# xmega_ethernet.net
KiCad netlist of a schematic drawn in EAGLE
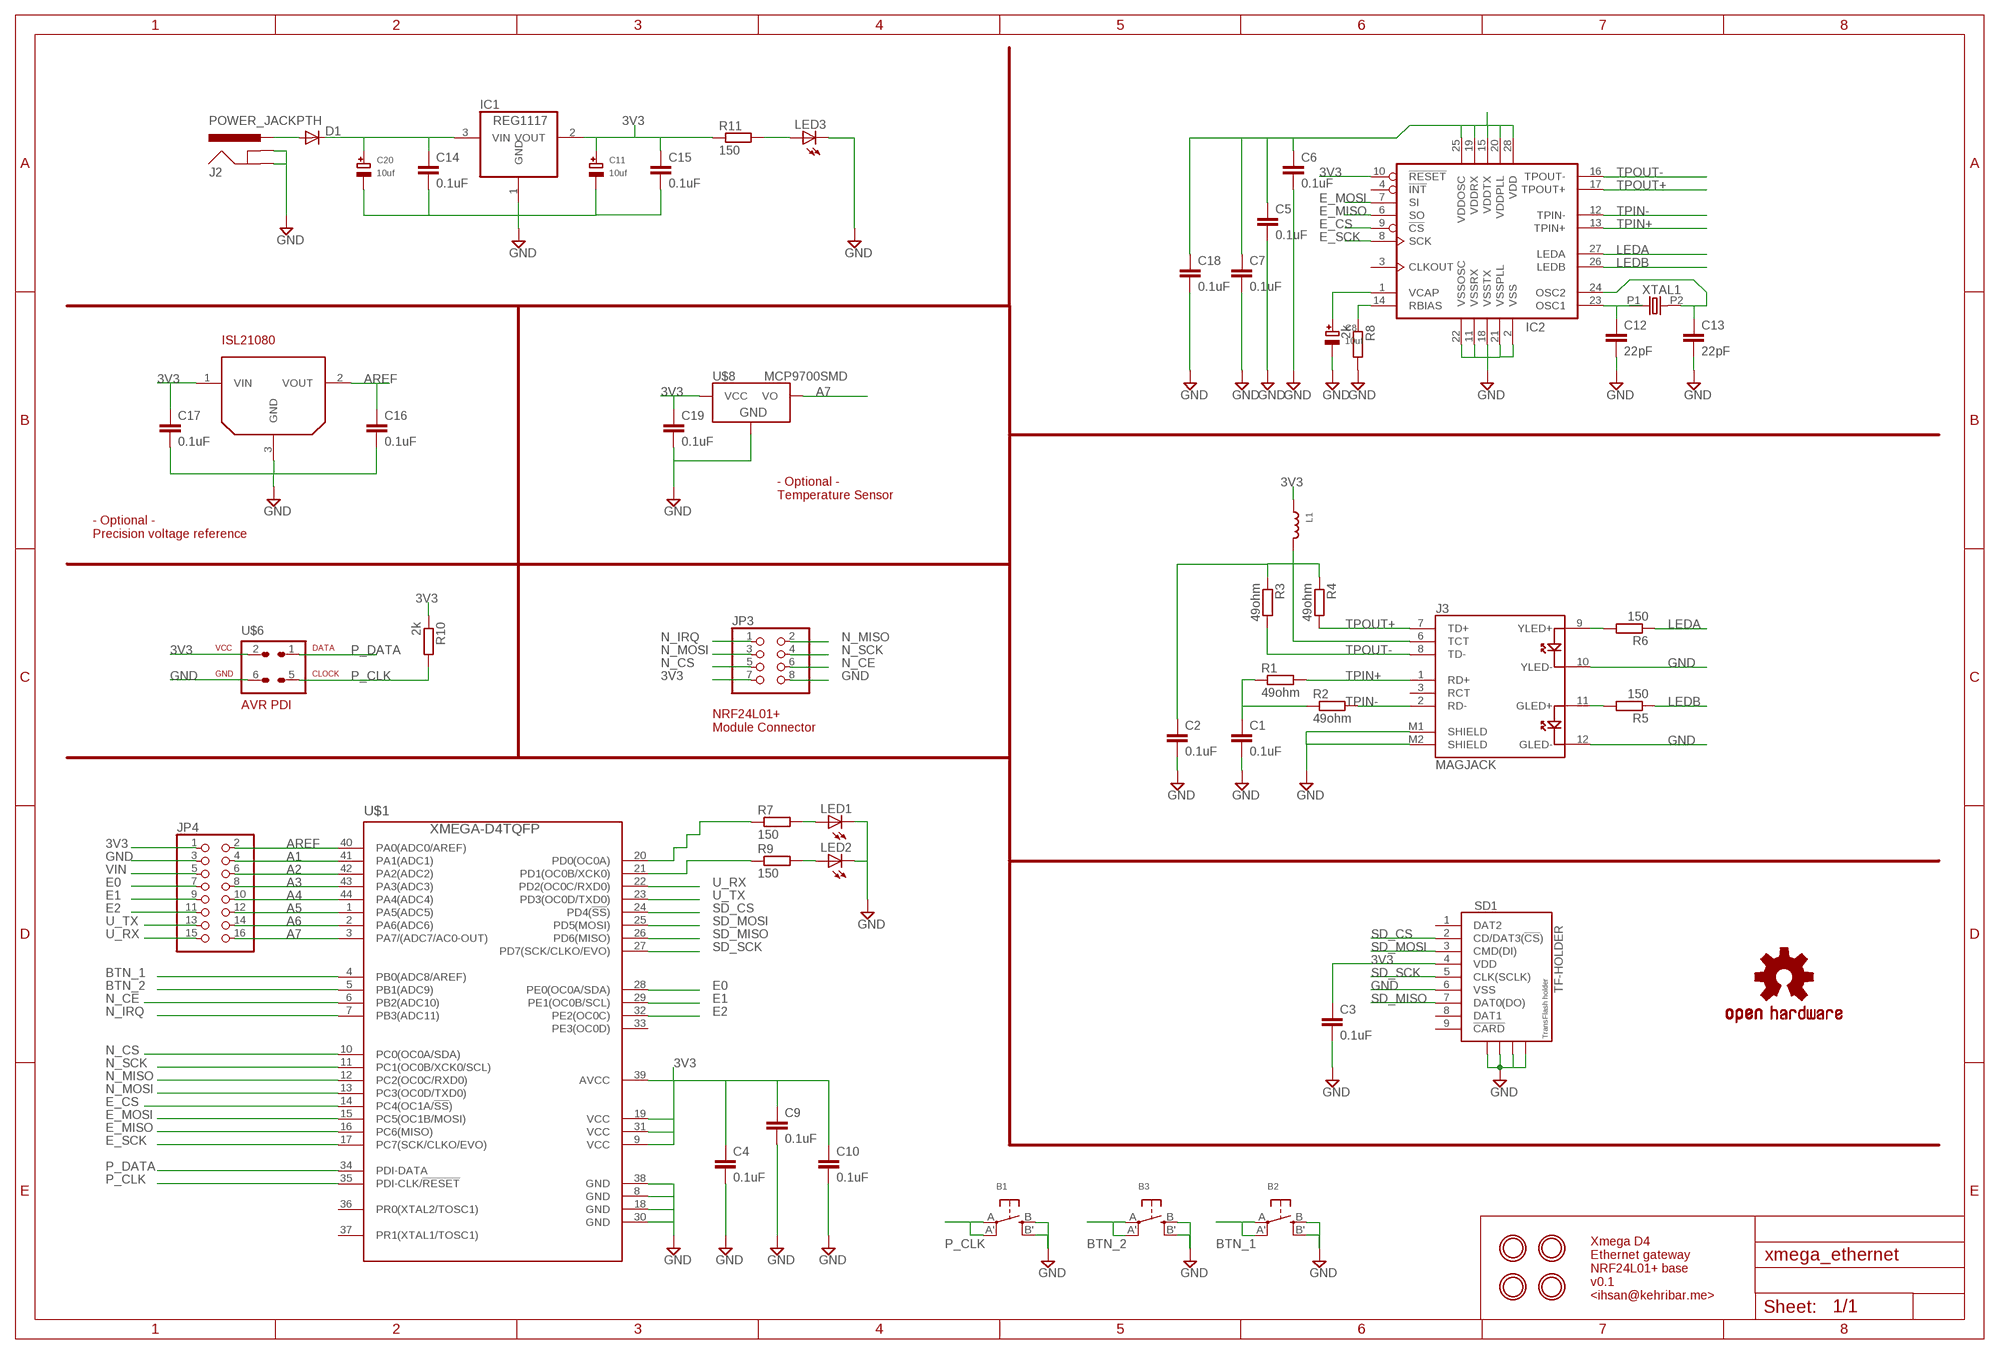
[diagram p0: schematic, sheet 1]

(export (version "E")
  (design (tool "Eeschema 10.0.6"))
  (components
    (comp (ref "B1")
      (value "SWITCH_TACT_SMT4.6X2.8")
      (footprint "eagle-import:BTN_KMR2_4.6X2.8")
      (libsource (lib "eagle-import") (part "SWITCH_TACT_SMT4.6X2.8"))
    )
    (comp (ref "B2")
      (value "SWITCH_TACT_SMT4.6X2.8")
      (footprint "eagle-import:BTN_KMR2_4.6X2.8")
      (libsource (lib "eagle-import") (part "SWITCH_TACT_SMT4.6X2.8"))
    )
    (comp (ref "B3")
      (value "SWITCH_TACT_SMT4.6X2.8")
      (footprint "eagle-import:BTN_KMR2_4.6X2.8")
      (libsource (lib "eagle-import") (part "SWITCH_TACT_SMT4.6X2.8"))
    )
    (comp (ref "C1")
      (value "0.1uF")
      (footprint "eagle-import:C0805")
      (libsource (lib "eagle-import") (part "C-EUC0805"))
    )
    (comp (ref "C2")
      (value "0.1uF")
      (footprint "eagle-import:C0805")
      (libsource (lib "eagle-import") (part "C-EUC0805"))
    )
    (comp (ref "C3")
      (value "0.1uF")
      (footprint "eagle-import:C0805")
      (libsource (lib "eagle-import") (part "C-EUC0805"))
    )
    (comp (ref "C4")
      (value "0.1uF")
      (footprint "eagle-import:C0805")
      (libsource (lib "eagle-import") (part "C-EUC0805"))
    )
    (comp (ref "C5")
      (value "0.1uF")
      (footprint "eagle-import:C0805")
      (libsource (lib "eagle-import") (part "C-EUC0805"))
    )
    (comp (ref "C6")
      (value "0.1uF")
      (footprint "eagle-import:C0805")
      (libsource (lib "eagle-import") (part "C-EUC0805"))
    )
    (comp (ref "C7")
      (value "0.1uF")
      (footprint "eagle-import:C0805")
      (libsource (lib "eagle-import") (part "C-EUC0805"))
    )
    (comp (ref "C8")
      (value "10uf")
      (footprint "eagle-import:EIA3528-21_B-W")
      (libsource (lib "eagle-import") (part "CAP_TANTALUMB/3528_WAVE"))
    )
    (comp (ref "C9")
      (value "0.1uF")
      (footprint "eagle-import:C0805")
      (libsource (lib "eagle-import") (part "C-EUC0805"))
    )
    (comp (ref "C10")
      (value "0.1uF")
      (footprint "eagle-import:C0805")
      (libsource (lib "eagle-import") (part "C-EUC0805"))
    )
    (comp (ref "C11")
      (value "10uf")
      (footprint "eagle-import:EIA3528-21_B-W")
      (libsource (lib "eagle-import") (part "CAP_TANTALUMB/3528_WAVE"))
    )
    (comp (ref "C12")
      (value "22pF")
      (footprint "eagle-import:C0805")
      (libsource (lib "eagle-import") (part "C-EUC0805"))
    )
    (comp (ref "C13")
      (value "22pF")
      (footprint "eagle-import:C0805")
      (libsource (lib "eagle-import") (part "C-EUC0805"))
    )
    (comp (ref "C14")
      (value "0.1uF")
      (footprint "eagle-import:C0805")
      (libsource (lib "eagle-import") (part "C-EUC0805"))
    )
    (comp (ref "C15")
      (value "0.1uF")
      (footprint "eagle-import:C0805")
      (libsource (lib "eagle-import") (part "C-EUC0805"))
    )
    (comp (ref "C16")
      (value "0.1uF")
      (footprint "eagle-import:C0805")
      (libsource (lib "eagle-import") (part "C-EUC0805"))
    )
    (comp (ref "C17")
      (value "0.1uF")
      (footprint "eagle-import:C0805")
      (libsource (lib "eagle-import") (part "C-EUC0805"))
    )
    (comp (ref "C18")
      (value "0.1uF")
      (footprint "eagle-import:C0805")
      (libsource (lib "eagle-import") (part "C-EUC0805"))
    )
    (comp (ref "C19")
      (value "0.1uF")
      (footprint "eagle-import:C0805")
      (libsource (lib "eagle-import") (part "C-EUC0805"))
    )
    (comp (ref "C20")
      (value "10uf")
      (footprint "eagle-import:EIA3528-21_B-W")
      (libsource (lib "eagle-import") (part "CAP_TANTALUMB/3528_WAVE"))
    )
    (comp (ref "D1")
      (value "DIODE1N4148")
      (footprint "eagle-import:DIODE-1N4148")
      (libsource (lib "eagle-import") (part "DIODE1N4148"))
    )
    (comp (ref "IC1")
      (value "REG1117")
      (footprint "eagle-import:SOT223")
      (libsource (lib "eagle-import") (part "REG1117"))
    )
    (comp (ref "IC2")
      (value "IC_ENC28J60-SOIC-28")
      (footprint "eagle-import:SOIC-28W")
      (libsource (lib "eagle-import") (part "IC_ENC28J60-SOIC-28"))
    )
    (comp (ref "J2")
      (value "POWER_JACKPTH")
      (footprint "eagle-import:POWER_JACK_PTH")
      (libsource (lib "eagle-import") (part "POWER_JACKPTH"))
    )
    (comp (ref "J3")
      (value "MAGJACK")
      (footprint "eagle-import:MAGJACK")
      (libsource (lib "eagle-import") (part "MAGJACK"))
    )
    (comp (ref "JP3")
      (value "PINHD-2X4")
      (footprint "eagle-import:2X04")
      (libsource (lib "eagle-import") (part "PINHD-2X4"))
    )
    (comp (ref "JP4")
      (value "PINHD-2X8")
      (footprint "eagle-import:2X08")
      (libsource (lib "eagle-import") (part "PINHD-2X8"))
    )
    (comp (ref "L1")
      (value "INDUCTOR0805")
      (footprint "eagle-import:0805")
      (libsource (lib "eagle-import") (part "INDUCTOR0805"))
    )
    (comp (ref "LED1")
      (value "LED-0805")
      (footprint "eagle-import:LED-805")
      (libsource (lib "eagle-import") (part "LED-0805"))
    )
    (comp (ref "LED2")
      (value "LED-0805")
      (footprint "eagle-import:LED-805")
      (libsource (lib "eagle-import") (part "LED-0805"))
    )
    (comp (ref "LED3")
      (value "LED-0805")
      (footprint "eagle-import:LED-805")
      (libsource (lib "eagle-import") (part "LED-0805"))
    )
    (comp (ref "LOGO1")
      (value "OSHW-LOGOM")
      (footprint "eagle-import:OSHW-LOGO-M")
      (libsource (lib "eagle-import") (part "OSHW-LOGOM"))
    )
    (comp (ref "R1")
      (value "49ohm")
      (footprint "eagle-import:R0805")
      (libsource (lib "eagle-import") (part "R-EU_R0805"))
    )
    (comp (ref "R2")
      (value "49ohm")
      (footprint "eagle-import:R0805")
      (libsource (lib "eagle-import") (part "R-EU_R0805"))
    )
    (comp (ref "R3")
      (value "49ohm")
      (footprint "eagle-import:R0805")
      (libsource (lib "eagle-import") (part "R-EU_R0805"))
    )
    (comp (ref "R4")
      (value "49ohm")
      (footprint "eagle-import:R0805")
      (libsource (lib "eagle-import") (part "R-EU_R0805"))
    )
    (comp (ref "R5")
      (value "150")
      (footprint "eagle-import:R0805")
      (libsource (lib "eagle-import") (part "R-EU_R0805"))
    )
    (comp (ref "R6")
      (value "150")
      (footprint "eagle-import:R0805")
      (libsource (lib "eagle-import") (part "R-EU_R0805"))
    )
    (comp (ref "R7")
      (value "150")
      (footprint "eagle-import:R0805")
      (libsource (lib "eagle-import") (part "R-EU_R0805"))
    )
    (comp (ref "R8")
      (value "2k")
      (footprint "eagle-import:R0805")
      (libsource (lib "eagle-import") (part "R-EU_R0805"))
    )
    (comp (ref "R9")
      (value "150")
      (footprint "eagle-import:R0805")
      (libsource (lib "eagle-import") (part "R-EU_R0805"))
    )
    (comp (ref "R10")
      (value "2k")
      (footprint "eagle-import:R0805")
      (libsource (lib "eagle-import") (part "R-EU_R0805"))
    )
    (comp (ref "R11")
      (value "150")
      (footprint "eagle-import:R0805")
      (libsource (lib "eagle-import") (part "R-EU_R0805"))
    )
    (comp (ref "SD1")
      (value "TF-HOLDER")
      (footprint "eagle-import:TF-PULL")
      (libsource (lib "eagle-import") (part "TF-HOLDER"))
    )
    (comp (ref "U$1")
      (value "XMEGA-D4TQFP")
      (footprint "eagle-import:TQFP44")
      (libsource (lib "eagle-import") (part "XMEGA-D4TQFP"))
    )
    (comp (ref "U$2")
      (value "MOUNTINGHOLE3.0THIN")
      (footprint "eagle-import:MOUNTINGHOLE_3.0_PLATEDTHIN")
      (libsource (lib "eagle-import") (part "MOUNTINGHOLE3.0THIN"))
    )
    (comp (ref "U$3")
      (value "MOUNTINGHOLE3.0THIN")
      (footprint "eagle-import:MOUNTINGHOLE_3.0_PLATEDTHIN")
      (libsource (lib "eagle-import") (part "MOUNTINGHOLE3.0THIN"))
    )
    (comp (ref "U$4")
      (value "MOUNTINGHOLE3.0THIN")
      (footprint "eagle-import:MOUNTINGHOLE_3.0_PLATEDTHIN")
      (libsource (lib "eagle-import") (part "MOUNTINGHOLE3.0THIN"))
    )
    (comp (ref "U$5")
      (value "MOUNTINGHOLE3.0THIN")
      (footprint "eagle-import:MOUNTINGHOLE_3.0_PLATEDTHIN")
      (libsource (lib "eagle-import") (part "MOUNTINGHOLE3.0THIN"))
    )
    (comp (ref "U$6")
      (value "AVR-PDIVERT")
      (footprint "eagle-import:AVR-ISP-6")
      (libsource (lib "eagle-import") (part "AVR-PDIVERT"))
    )
    (comp (ref "U$7")
      (value "IHSAN_ISL21080")
      (footprint "eagle-import:SOT23-3")
      (libsource (lib "eagle-import") (part "IHSAN_ISL21080"))
    )
    (comp (ref "U$8")
      (value "MCP9700SMD")
      (footprint "eagle-import:SOT23-3")
      (libsource (lib "eagle-import") (part "MCP9700SMD"))
    )
    (comp (ref "XTAL1")
      (value "OSC-XTAL-HC-49U-PTH")
      (footprint "eagle-import:HC-49U-PTH")
      (libsource (lib "eagle-import") (part "OSC-XTAL-HC-49U-PTH"))
    )
  )
  (nets
    (net (code "1") (name "/3V3") (class "Default")
      (node (ref "C10") (pin "1") (pinfunction "1_1") (pintype "passive"))
      (node (ref "C11") (pin "+") (pinfunction "+_+") (pintype "passive"))
      (node (ref "C15") (pin "1") (pinfunction "1_1") (pintype "passive"))
      (node (ref "C17") (pin "1") (pinfunction "1_1") (pintype "passive"))
      (node (ref "C18") (pin "1") (pinfunction "1_1") (pintype "passive"))
      (node (ref "C19") (pin "1") (pinfunction "1_1") (pintype "passive"))
      (node (ref "C3") (pin "1") (pinfunction "1_1") (pintype "passive"))
      (node (ref "C4") (pin "1") (pinfunction "1_1") (pintype "passive"))
      (node (ref "C5") (pin "1") (pinfunction "1_1") (pintype "passive"))
      (node (ref "C6") (pin "1") (pinfunction "1_1") (pintype "passive"))
      (node (ref "C7") (pin "1") (pinfunction "1_1") (pintype "passive"))
      (node (ref "C9") (pin "1") (pinfunction "1_1") (pintype "passive"))
      (node (ref "IC1") (pin "2") (pinfunction "VOUT_2") (pintype "output"))
      (node (ref "IC2") (pin "10") (pinfunction "~{RESET}_10") (pintype "input"))
      (node (ref "IC2") (pin "15") (pinfunction "VDDTX_15") (pintype "power_in"))
      (node (ref "IC2") (pin "19") (pinfunction "VDDRX_19") (pintype "power_in"))
      (node (ref "IC2") (pin "20") (pinfunction "VDDPLL_20") (pintype "power_in"))
      (node (ref "IC2") (pin "25") (pinfunction "VDDOSC_25") (pintype "power_in"))
      (node (ref "IC2") (pin "28") (pinfunction "VDD_28") (pintype "power_in"))
      (node (ref "JP3") (pin "7") (pinfunction "7_7") (pintype "passive"))
      (node (ref "JP4") (pin "1") (pinfunction "1_1") (pintype "passive"))
      (node (ref "L1") (pin "1") (pinfunction "1_1") (pintype "passive"))
      (node (ref "R10") (pin "1") (pinfunction "1_1") (pintype "passive"))
      (node (ref "R11") (pin "1") (pinfunction "1_1") (pintype "passive"))
      (node (ref "SD1") (pin "4") (pinfunction "VDD_4") (pintype "power_in"))
      (node (ref "U$1") (pin "19") (pinfunction "VCC_19") (pintype "power_in"))
      (node (ref "U$1") (pin "31") (pinfunction "VCC_31") (pintype "power_in"))
      (node (ref "U$1") (pin "39") (pinfunction "AVCC_39") (pintype "power_in"))
      (node (ref "U$1") (pin "9") (pinfunction "VCC_9") (pintype "power_in"))
      (node (ref "U$6") (pin "2") (pinfunction "2_2") (pintype "passive"))
      (node (ref "U$7") (pin "1") (pinfunction "VIN_1") (pintype "bidirectional"))
      (node (ref "U$8") (pin "1") (pinfunction "VCC_1") (pintype "bidirectional"))
    )
    (net (code "2") (name "/A1") (class "Default")
      (node (ref "JP4") (pin "4") (pinfunction "4_4") (pintype "passive"))
      (node (ref "U$1") (pin "41") (pinfunction "PA1(ADC1)_41") (pintype "bidirectional"))
    )
    (net (code "3") (name "/A2") (class "Default")
      (node (ref "JP4") (pin "6") (pinfunction "6_6") (pintype "passive"))
      (node (ref "U$1") (pin "42") (pinfunction "PA2(ADC2)_42") (pintype "bidirectional"))
    )
    (net (code "4") (name "/A3") (class "Default")
      (node (ref "JP4") (pin "8") (pinfunction "8_8") (pintype "passive"))
      (node (ref "U$1") (pin "43") (pinfunction "PA3(ADC3)_43") (pintype "bidirectional"))
    )
    (net (code "5") (name "/A4") (class "Default")
      (node (ref "JP4") (pin "10") (pinfunction "10_10") (pintype "passive"))
      (node (ref "U$1") (pin "44") (pinfunction "PA4(ADC4)_44") (pintype "bidirectional"))
    )
    (net (code "6") (name "/A5") (class "Default")
      (node (ref "JP4") (pin "12") (pinfunction "12_12") (pintype "passive"))
      (node (ref "U$1") (pin "1") (pinfunction "PA5(ADC5)_1") (pintype "bidirectional"))
    )
    (net (code "7") (name "/A6") (class "Default")
      (node (ref "JP4") (pin "14") (pinfunction "14_14") (pintype "passive"))
      (node (ref "U$1") (pin "2") (pinfunction "PA6(ADC6)_2") (pintype "bidirectional"))
    )
    (net (code "8") (name "/A7") (class "Default")
      (node (ref "JP4") (pin "16") (pinfunction "16_16") (pintype "passive"))
      (node (ref "U$1") (pin "3") (pinfunction "PA7/(ADC7/AC0-OUT)_3") (pintype "bidirectional"))
      (node (ref "U$8") (pin "2") (pinfunction "VO_2") (pintype "bidirectional"))
    )
    (net (code "9") (name "/AREF") (class "Default")
      (node (ref "C16") (pin "1") (pinfunction "1_1") (pintype "passive"))
      (node (ref "JP4") (pin "2") (pinfunction "2_2") (pintype "passive"))
      (node (ref "U$1") (pin "40") (pinfunction "PA0(ADC0/AREF)_40") (pintype "bidirectional"))
      (node (ref "U$7") (pin "2") (pinfunction "VOUT_2") (pintype "bidirectional"))
    )
    (net (code "10") (name "/BTN_1") (class "Default")
      (node (ref "B2") (pin "A") (pinfunction "P_A") (pintype "passive"))
      (node (ref "B2") (pin "A'") (pinfunction "P1_A'") (pintype "passive"))
      (node (ref "U$1") (pin "4") (pinfunction "PB0(ADC8/AREF)_4") (pintype "bidirectional"))
    )
    (net (code "11") (name "/BTN_2") (class "Default")
      (node (ref "B3") (pin "A") (pinfunction "P_A") (pintype "passive"))
      (node (ref "B3") (pin "A'") (pinfunction "P1_A'") (pintype "passive"))
      (node (ref "U$1") (pin "5") (pinfunction "PB1(ADC9)_5") (pintype "bidirectional"))
    )
    (net (code "12") (name "/E0") (class "Default")
      (node (ref "JP4") (pin "7") (pinfunction "7_7") (pintype "passive"))
      (node (ref "U$1") (pin "28") (pinfunction "PE0(OC0A/SDA)_28") (pintype "bidirectional"))
    )
    (net (code "13") (name "/E1") (class "Default")
      (node (ref "JP4") (pin "9") (pinfunction "9_9") (pintype "passive"))
      (node (ref "U$1") (pin "29") (pinfunction "PE1(OC0B/SCL)_29") (pintype "bidirectional"))
    )
    (net (code "14") (name "/E2") (class "Default")
      (node (ref "JP4") (pin "11") (pinfunction "11_11") (pintype "passive"))
      (node (ref "U$1") (pin "32") (pinfunction "PE2(OC0C)_32") (pintype "bidirectional"))
    )
    (net (code "15") (name "/E_CS") (class "Default")
      (node (ref "IC2") (pin "9") (pinfunction "~{CS}_9") (pintype "input"))
      (node (ref "U$1") (pin "14") (pinfunction "PC4(OC1A/~{SS})_14") (pintype "bidirectional"))
    )
    (net (code "16") (name "/E_MISO") (class "Default")
      (node (ref "IC2") (pin "6") (pinfunction "SO_6") (pintype "output"))
      (node (ref "U$1") (pin "16") (pinfunction "PC6(MISO)_16") (pintype "bidirectional"))
    )
    (net (code "17") (name "/E_MOSI") (class "Default")
      (node (ref "IC2") (pin "7") (pinfunction "SI_7") (pintype "input"))
      (node (ref "U$1") (pin "15") (pinfunction "PC5(OC1B/MOSI)_15") (pintype "bidirectional"))
    )
    (net (code "18") (name "/E_SCK") (class "Default")
      (node (ref "IC2") (pin "8") (pinfunction "SCK_8") (pintype "input"))
      (node (ref "U$1") (pin "17") (pinfunction "PC7(SCK/CLKO/EVO)_17") (pintype "bidirectional"))
    )
    (net (code "19") (name "/LEDA") (class "Default")
      (node (ref "IC2") (pin "27") (pinfunction "LEDA_27") (pintype "output"))
      (node (ref "R6") (pin "1") (pinfunction "1_1") (pintype "passive"))
    )
    (net (code "20") (name "/LEDB") (class "Default")
      (node (ref "IC2") (pin "26") (pinfunction "LEDB_26") (pintype "output"))
      (node (ref "R5") (pin "1") (pinfunction "1_1") (pintype "passive"))
    )
    (net (code "21") (name "/N_CE") (class "Default")
      (node (ref "JP3") (pin "6") (pinfunction "6_6") (pintype "passive"))
      (node (ref "U$1") (pin "6") (pinfunction "PB2(ADC10)_6") (pintype "bidirectional"))
    )
    (net (code "22") (name "/N_CS") (class "Default")
      (node (ref "JP3") (pin "5") (pinfunction "5_5") (pintype "passive"))
      (node (ref "U$1") (pin "10") (pinfunction "PC0(OC0A/SDA)_10") (pintype "bidirectional"))
    )
    (net (code "23") (name "/N_IRQ") (class "Default")
      (node (ref "JP3") (pin "1") (pinfunction "1_1") (pintype "passive"))
      (node (ref "U$1") (pin "7") (pinfunction "PB3(ADC11)_7") (pintype "bidirectional"))
    )
    (net (code "24") (name "/N_MISO") (class "Default")
      (node (ref "JP3") (pin "2") (pinfunction "2_2") (pintype "passive"))
      (node (ref "U$1") (pin "12") (pinfunction "PC2(OC0C/RXD0)_12") (pintype "bidirectional"))
    )
    (net (code "25") (name "/N_MOSI") (class "Default")
      (node (ref "JP3") (pin "3") (pinfunction "3_3") (pintype "passive"))
      (node (ref "U$1") (pin "13") (pinfunction "PC3(OC0D/TXD0)_13") (pintype "bidirectional"))
    )
    (net (code "26") (name "/N_SCK") (class "Default")
      (node (ref "JP3") (pin "4") (pinfunction "4_4") (pintype "passive"))
      (node (ref "U$1") (pin "11") (pinfunction "PC1(OC0B/XCK0/SCL)_11") (pintype "bidirectional"))
    )
    (net (code "27") (name "/P_CLK") (class "Default")
      (node (ref "B1") (pin "A") (pinfunction "P_A") (pintype "passive"))
      (node (ref "B1") (pin "A'") (pinfunction "P1_A'") (pintype "passive"))
      (node (ref "R10") (pin "2") (pinfunction "2_2") (pintype "passive"))
      (node (ref "U$1") (pin "35") (pinfunction "PDI-CLK/~{RESET}_35") (pintype "input"))
      (node (ref "U$6") (pin "5") (pinfunction "5_5") (pintype "passive"))
    )
    (net (code "28") (name "/P_DATA") (class "Default")
      (node (ref "U$1") (pin "34") (pinfunction "PDI-DATA_34") (pintype "bidirectional"))
      (node (ref "U$6") (pin "1") (pinfunction "1_1") (pintype "passive"))
    )
    (net (code "29") (name "/SD_CS") (class "Default")
      (node (ref "SD1") (pin "2") (pinfunction "CD/DAT3(~{CS})_2") (pintype "bidirectional"))
      (node (ref "U$1") (pin "24") (pinfunction "PD4(~{SS})_24") (pintype "bidirectional"))
    )
    (net (code "30") (name "/SD_MISO") (class "Default")
      (node (ref "SD1") (pin "7") (pinfunction "DAT0(DO)_7") (pintype "bidirectional"))
      (node (ref "U$1") (pin "26") (pinfunction "PD6(MISO)_26") (pintype "bidirectional"))
    )
    (net (code "31") (name "/SD_MOSI") (class "Default")
      (node (ref "SD1") (pin "3") (pinfunction "CMD(DI)_3") (pintype "bidirectional"))
      (node (ref "U$1") (pin "25") (pinfunction "PD5(MOSI)_25") (pintype "bidirectional"))
    )
    (net (code "32") (name "/SD_SCK") (class "Default")
      (node (ref "SD1") (pin "5") (pinfunction "CLK(SCLK)_5") (pintype "input"))
      (node (ref "U$1") (pin "27") (pinfunction "PD7(SCK/CLKO/EVO)_27") (pintype "bidirectional"))
    )
    (net (code "33") (name "/TPIN+") (class "Default")
      (node (ref "IC2") (pin "13") (pinfunction "TPIN+_13") (pintype "input"))
      (node (ref "J3") (pin "1") (pinfunction "RD+_1") (pintype "bidirectional"))
      (node (ref "R1") (pin "2") (pinfunction "2_2") (pintype "passive"))
    )
    (net (code "34") (name "/TPIN-") (class "Default")
      (node (ref "IC2") (pin "12") (pinfunction "TPIN-_12") (pintype "input"))
      (node (ref "J3") (pin "2") (pinfunction "RD-_2") (pintype "bidirectional"))
      (node (ref "R2") (pin "2") (pinfunction "2_2") (pintype "passive"))
    )
    (net (code "35") (name "/TPOUT+") (class "Default")
      (node (ref "IC2") (pin "17") (pinfunction "TPOUT+_17") (pintype "output"))
      (node (ref "J3") (pin "7") (pinfunction "TD+_7") (pintype "bidirectional"))
      (node (ref "R4") (pin "2") (pinfunction "2_2") (pintype "passive"))
    )
    (net (code "36") (name "/TPOUT-") (class "Default")
      (node (ref "IC2") (pin "16") (pinfunction "TPOUT-_16") (pintype "output"))
      (node (ref "J3") (pin "8") (pinfunction "TD-_8") (pintype "bidirectional"))
      (node (ref "R3") (pin "2") (pinfunction "2_2") (pintype "passive"))
    )
    (net (code "37") (name "/U_RX") (class "Default")
      (node (ref "JP4") (pin "15") (pinfunction "15_15") (pintype "passive"))
      (node (ref "U$1") (pin "22") (pinfunction "PD2(OC0C/RXD0)_22") (pintype "bidirectional"))
    )
    (net (code "38") (name "/U_TX") (class "Default")
      (node (ref "JP4") (pin "13") (pinfunction "13_13") (pintype "passive"))
      (node (ref "U$1") (pin "23") (pinfunction "PD3(OC0D/TXD0)_23") (pintype "bidirectional"))
    )
    (net (code "39") (name "/VIN") (class "Default")
      (node (ref "C14") (pin "1") (pinfunction "1_1") (pintype "passive"))
      (node (ref "C20") (pin "+") (pinfunction "+_+") (pintype "passive"))
      (node (ref "D1") (pin "C") (pinfunction "C_C") (pintype "passive"))
      (node (ref "IC1") (pin "3") (pinfunction "VIN_3") (pintype "input"))
      (node (ref "JP4") (pin "5") (pinfunction "5_5") (pintype "passive"))
    )
    (net (code "40") (name "GND") (class "Default")
      (node (ref "B1") (pin "B") (pinfunction "S_B") (pintype "passive"))
      (node (ref "B1") (pin "B'") (pinfunction "S1_B'") (pintype "passive"))
      (node (ref "B2") (pin "B") (pinfunction "S_B") (pintype "passive"))
      (node (ref "B2") (pin "B'") (pinfunction "S1_B'") (pintype "passive"))
      (node (ref "B3") (pin "B") (pinfunction "S_B") (pintype "passive"))
      (node (ref "B3") (pin "B'") (pinfunction "S1_B'") (pintype "passive"))
      (node (ref "C1") (pin "2") (pinfunction "2_2") (pintype "passive"))
      (node (ref "C10") (pin "2") (pinfunction "2_2") (pintype "passive"))
      (node (ref "C11") (pin "-") (pinfunction "-_-") (pintype "passive"))
      (node (ref "C12") (pin "2") (pinfunction "2_2") (pintype "passive"))
      (node (ref "C13") (pin "2") (pinfunction "2_2") (pintype "passive"))
      (node (ref "C14") (pin "2") (pinfunction "2_2") (pintype "passive"))
      (node (ref "C15") (pin "2") (pinfunction "2_2") (pintype "passive"))
      (node (ref "C16") (pin "2") (pinfunction "2_2") (pintype "passive"))
      (node (ref "C17") (pin "2") (pinfunction "2_2") (pintype "passive"))
      (node (ref "C18") (pin "2") (pinfunction "2_2") (pintype "passive"))
      (node (ref "C19") (pin "2") (pinfunction "2_2") (pintype "passive"))
      (node (ref "C2") (pin "2") (pinfunction "2_2") (pintype "passive"))
      (node (ref "C20") (pin "-") (pinfunction "-_-") (pintype "passive"))
      (node (ref "C3") (pin "2") (pinfunction "2_2") (pintype "passive"))
      (node (ref "C4") (pin "2") (pinfunction "2_2") (pintype "passive"))
      (node (ref "C5") (pin "2") (pinfunction "2_2") (pintype "passive"))
      (node (ref "C6") (pin "2") (pinfunction "2_2") (pintype "passive"))
      (node (ref "C7") (pin "2") (pinfunction "2_2") (pintype "passive"))
      (node (ref "C8") (pin "-") (pinfunction "-_-") (pintype "passive"))
      (node (ref "C9") (pin "2") (pinfunction "2_2") (pintype "passive"))
      (node (ref "IC1") (pin "1") (pinfunction "GND_1") (pintype "power_in"))
      (node (ref "IC2") (pin "11") (pinfunction "VSSRX_11") (pintype "power_in"))
      (node (ref "IC2") (pin "18") (pinfunction "VSSTX_18") (pintype "power_in"))
      (node (ref "IC2") (pin "2") (pinfunction "VSS_2") (pintype "power_in"))
      (node (ref "IC2") (pin "21") (pinfunction "VSSPLL_21") (pintype "power_in"))
      (node (ref "IC2") (pin "22") (pinfunction "VSSOSC_22") (pintype "power_in"))
      (node (ref "J2") (pin "GND") (pinfunction "GND_GND") (pintype "bidirectional"))
      (node (ref "J2") (pin "GNDBREAK") (pinfunction "GNDBREAK_GNDBREAK") (pintype "bidirectional"))
      (node (ref "J3") (pin "10") (pinfunction "YLED-_10") (pintype "bidirectional"))
      (node (ref "J3") (pin "12") (pinfunction "GLED-_12") (pintype "bidirectional"))
      (node (ref "J3") (pin "M1") (pinfunction "SHIELD_M1") (pintype "bidirectional"))
      (node (ref "J3") (pin "M2") (pinfunction "SHIELD_M2") (pintype "bidirectional"))
      (node (ref "JP3") (pin "8") (pinfunction "8_8") (pintype "passive"))
      (node (ref "JP4") (pin "3") (pinfunction "3_3") (pintype "passive"))
      (node (ref "LED1") (pin "C") (pinfunction "C_C") (pintype "passive"))
      (node (ref "LED2") (pin "C") (pinfunction "C_C") (pintype "passive"))
      (node (ref "LED3") (pin "C") (pinfunction "C_C") (pintype "passive"))
      (node (ref "R8") (pin "2") (pinfunction "2_2") (pintype "passive"))
      (node (ref "SD1") (pin "6") (pinfunction "VSS_6") (pintype "power_in"))
      (node (ref "SD1") (pin "S1") (pinfunction "S1_S1") (pintype "passive"))
      (node (ref "SD1") (pin "S2") (pinfunction "S2_S2") (pintype "passive"))
      (node (ref "SD1") (pin "S3") (pinfunction "S3_S3") (pintype "passive"))
      (node (ref "SD1") (pin "S4") (pinfunction "S4_S4") (pintype "passive"))
      (node (ref "U$1") (pin "18") (pinfunction "GND_18") (pintype "power_in"))
      (node (ref "U$1") (pin "30") (pinfunction "GND_30") (pintype "power_in"))
      (node (ref "U$1") (pin "38") (pinfunction "GND_38") (pintype "power_in"))
      (node (ref "U$1") (pin "8") (pinfunction "GND_8") (pintype "power_in"))
      (node (ref "U$6") (pin "6") (pinfunction "6_6") (pintype "passive"))
      (node (ref "U$7") (pin "3") (pinfunction "GND_3") (pintype "bidirectional"))
      (node (ref "U$8") (pin "3") (pinfunction "GND_3") (pintype "bidirectional"))
    )
    (net (code "41") (name "Net-(C1-Pad1)") (class "Default")
      (node (ref "C1") (pin "1") (pinfunction "1_1") (pintype "passive"))
      (node (ref "R1") (pin "1") (pinfunction "1_1") (pintype "passive"))
      (node (ref "R2") (pin "1") (pinfunction "1_1") (pintype "passive"))
    )
    (net (code "42") (name "Net-(D1-PadA)") (class "Default")
      (node (ref "D1") (pin "A") (pinfunction "A_A") (pintype "passive"))
      (node (ref "J2") (pin "PWR") (pinfunction "PWR_PWR") (pintype "bidirectional"))
    )
    (net (code "43") (name "Net-(IC2-OSC1)") (class "Default")
      (node (ref "C12") (pin "1") (pinfunction "1_1") (pintype "passive"))
      (node (ref "IC2") (pin "23") (pinfunction "OSC1_23") (pintype "input"))
      (node (ref "XTAL1") (pin "P1") (pinfunction "1_P1") (pintype "passive"))
    )
    (net (code "44") (name "Net-(IC2-OSC2)") (class "Default")
      (node (ref "C13") (pin "1") (pinfunction "1_1") (pintype "passive"))
      (node (ref "IC2") (pin "24") (pinfunction "OSC2_24") (pintype "output"))
      (node (ref "XTAL1") (pin "P2") (pinfunction "2_P2") (pintype "passive"))
    )
    (net (code "45") (name "Net-(IC2-RBIAS)") (class "Default")
      (node (ref "IC2") (pin "14") (pinfunction "RBIAS_14") (pintype "input"))
      (node (ref "R8") (pin "1") (pinfunction "1_1") (pintype "passive"))
    )
    (net (code "46") (name "Net-(IC2-VCAP)") (class "Default")
      (node (ref "C8") (pin "+") (pinfunction "+_+") (pintype "passive"))
      (node (ref "IC2") (pin "1") (pinfunction "VCAP_1") (pintype "input"))
    )
    (net (code "47") (name "Net-(J3-GLED+)") (class "Default")
      (node (ref "J3") (pin "11") (pinfunction "GLED+_11") (pintype "bidirectional"))
      (node (ref "R5") (pin "2") (pinfunction "2_2") (pintype "passive"))
    )
    (net (code "48") (name "Net-(J3-TCT)") (class "Default")
      (node (ref "C2") (pin "1") (pinfunction "1_1") (pintype "passive"))
      (node (ref "J3") (pin "6") (pinfunction "TCT_6") (pintype "bidirectional"))
      (node (ref "L1") (pin "2") (pinfunction "2_2") (pintype "passive"))
      (node (ref "R3") (pin "1") (pinfunction "1_1") (pintype "passive"))
      (node (ref "R4") (pin "1") (pinfunction "1_1") (pintype "passive"))
    )
    (net (code "49") (name "Net-(J3-YLED+)") (class "Default")
      (node (ref "J3") (pin "9") (pinfunction "YLED+_9") (pintype "bidirectional"))
      (node (ref "R6") (pin "2") (pinfunction "2_2") (pintype "passive"))
    )
    (net (code "50") (name "Net-(LED1-PadA)") (class "Default")
      (node (ref "LED1") (pin "A") (pinfunction "A_A") (pintype "passive"))
      (node (ref "R7") (pin "2") (pinfunction "2_2") (pintype "passive"))
    )
    (net (code "51") (name "Net-(LED2-PadA)") (class "Default")
      (node (ref "LED2") (pin "A") (pinfunction "A_A") (pintype "passive"))
      (node (ref "R9") (pin "2") (pinfunction "2_2") (pintype "passive"))
    )
    (net (code "52") (name "Net-(LED3-PadA)") (class "Default")
      (node (ref "LED3") (pin "A") (pinfunction "A_A") (pintype "passive"))
      (node (ref "R11") (pin "2") (pinfunction "2_2") (pintype "passive"))
    )
    (net (code "53") (name "Net-(U$1-PD0(OC0A))") (class "Default")
      (node (ref "R7") (pin "1") (pinfunction "1_1") (pintype "passive"))
      (node (ref "U$1") (pin "20") (pinfunction "PD0(OC0A)_20") (pintype "bidirectional"))
    )
    (net (code "54") (name "Net-(U$1-PD1(OC0B{slash}XCK0))") (class "Default")
      (node (ref "R9") (pin "1") (pinfunction "1_1") (pintype "passive"))
      (node (ref "U$1") (pin "21") (pinfunction "PD1(OC0B/XCK0)_21") (pintype "bidirectional"))
    )
    (net (code "55") (name "unconnected-(IC2-CLKOUT-Pad3)") (class "Default")
      (node (ref "IC2") (pin "3") (pinfunction "CLKOUT_3") (pintype "output"))
    )
    (net (code "56") (name "unconnected-(IC2-~{INT}-Pad4)") (class "Default")
      (node (ref "IC2") (pin "4") (pinfunction "~{INT}_4") (pintype "output"))
    )
    (net (code "57") (name "unconnected-(J3-RCT-Pad3)") (class "Default")
      (node (ref "J3") (pin "3") (pinfunction "RCT_3") (pintype "bidirectional"))
    )
    (net (code "58") (name "unconnected-(SD1-DAT1-Pad8)") (class "Default")
      (node (ref "SD1") (pin "8") (pinfunction "DAT1_8") (pintype "bidirectional"))
    )
    (net (code "59") (name "unconnected-(SD1-DAT2-Pad1)") (class "Default")
      (node (ref "SD1") (pin "1") (pinfunction "DAT2_1") (pintype "bidirectional"))
    )
    (net (code "60") (name "unconnected-(SD1-~{CARD}-Pad9)") (class "Default")
      (node (ref "SD1") (pin "9") (pinfunction "~{CARD}_9") (pintype "passive"))
    )
    (net (code "61") (name "unconnected-(U$1-PE3(OC0D)-Pad33)") (class "Default")
      (node (ref "U$1") (pin "33") (pinfunction "PE3(OC0D)_33") (pintype "bidirectional"))
    )
    (net (code "62") (name "unconnected-(U$1-PR0(XTAL2{slash}TOSC1)-Pad36)") (class "Default")
      (node (ref "U$1") (pin "36") (pinfunction "PR0(XTAL2/TOSC1)_36") (pintype "bidirectional"))
    )
    (net (code "63") (name "unconnected-(U$1-PR1(XTAL1{slash}TOSC1)-Pad37)") (class "Default")
      (node (ref "U$1") (pin "37") (pinfunction "PR1(XTAL1/TOSC1)_37") (pintype "bidirectional"))
    )
  )
)
